# LVDS_repeater.net
KiCad netlist of a schematic drawn in Altium Designer
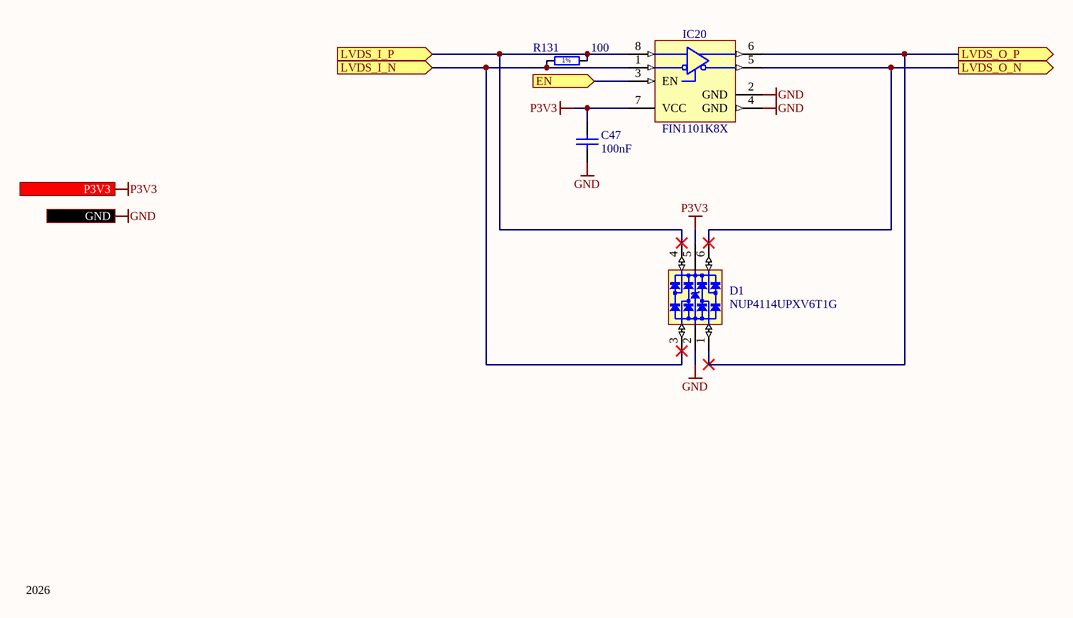
[diagram p0: LVDS_repeater.SchDoc]

(export (version "E")
  (design (tool "Eeschema 10.0.6"))
  (components
    (comp (ref "C47")
      (value "100nF")
      (footprint "CAPC1005X55N")
      (description "Non-polarised capacitor")
      (fields
        (field (name "PART NUMBER") "CC0402_100NF_50V_10%_X7R")
        (field (name "VOLTAGE") "50V")
        (field (name "AUTHOR") "CERN DEM MR")
      )
      (libsource (lib "Capacitors") (part "Capacitor - non polarized"))
    )
    (comp (ref "D1")
      (value "NUP4114UPXV6T1G")
      (footprint "SOTFL50P160X60-6N")
      (description "ESD Protection Diodes Array (8kV) with Low Clamping Voltage")
      (fields
        (field (name "VOLTAGE") "5.5V")
        (field (name "MANUFACTURER") "ON SEMICONDUCTOR")
        (field (name "AUTHOR") "CERN DEM JLC")
      )
      (libsource (lib "ICs And Semiconductors") (part "NUP4114"))
    )
    (comp (ref "IC20")
      (value "FIN1101K8X")
      (footprint "SOP50P310X90-8N")
      (description "LVDS Single Port High Speed Repeater")
      (fields (field (name "MANUFACTURER") "FAIRCHILD SEMICONDUCTOR") (field (name "AUTHOR") "CERN DEM JLC"))
      (libsource (lib "ICs And Semiconductors") (part "FIN1101K8X"))
    )
    (comp (ref "R131")
      (value "100")
      (footprint "RESC1005X40N")
      (description "Resistor - 1%")
      (fields
        (field (name "PART NUMBER") "R0402_100R_1%_0.1W_100PPM")
        (field (name "POWER") "0.1W")
        (field (name "AUTHOR") "CERN DEM JLC")
      )
      (libsource (lib "Resistors") (part "Resistor - 1%"))
    )
  )
  (nets
    (net (code "1") (name "/EN") (class "Default")
      (node (ref "IC20") (pin "3") (pinfunction "EN_3") (pintype "input"))
    )
    (net (code "2") (name "/LVDS_I_N") (class "Default")
      (node (ref "D1") (pin "3") (pinfunction "I/O2_3") (pintype "bidirectional"))
      (node (ref "IC20") (pin "1") (pinfunction "RIN-_1") (pintype "input"))
      (node (ref "R131") (pin "1") (pinfunction "1_1") (pintype "passive"))
    )
    (net (code "3") (name "/LVDS_I_P") (class "Default")
      (node (ref "D1") (pin "4") (pinfunction "I/O3_4") (pintype "bidirectional"))
      (node (ref "IC20") (pin "8") (pinfunction "RIN+_8") (pintype "input"))
      (node (ref "R131") (pin "2") (pinfunction "2_2") (pintype "passive"))
    )
    (net (code "4") (name "/LVDS_O_N") (class "Default")
      (node (ref "D1") (pin "6") (pinfunction "I/O4_6") (pintype "bidirectional"))
      (node (ref "IC20") (pin "5") (pinfunction "DOUT-_5") (pintype "output"))
    )
    (net (code "5") (name "/LVDS_O_P") (class "Default")
      (node (ref "D1") (pin "1") (pinfunction "I/O1_1") (pintype "bidirectional"))
      (node (ref "IC20") (pin "6") (pinfunction "DOUT+_6") (pintype "output"))
    )
    (net (code "6") (name "GND") (class "Default")
      (node (ref "C47") (pin "1") (pinfunction "1_1") (pintype "passive"))
      (node (ref "D1") (pin "2") (pinfunction "GND_2") (pintype "power_in"))
      (node (ref "IC20") (pin "2") (pinfunction "GND_2") (pintype "power_in"))
      (node (ref "IC20") (pin "4") (pinfunction "GND_4") (pintype "output"))
    )
    (net (code "7") (name "P3V3") (class "Default")
      (node (ref "C47") (pin "2") (pinfunction "2_2") (pintype "passive"))
      (node (ref "D1") (pin "5") (pinfunction "VBUS_5") (pintype "power_in"))
      (node (ref "IC20") (pin "7") (pinfunction "VCC_7") (pintype "power_in"))
    )
  )
)
